# lm3410-sepic-flashlight-driver-17mm-mk-1.net
KiCad netlist of a schematic drawn in EAGLE
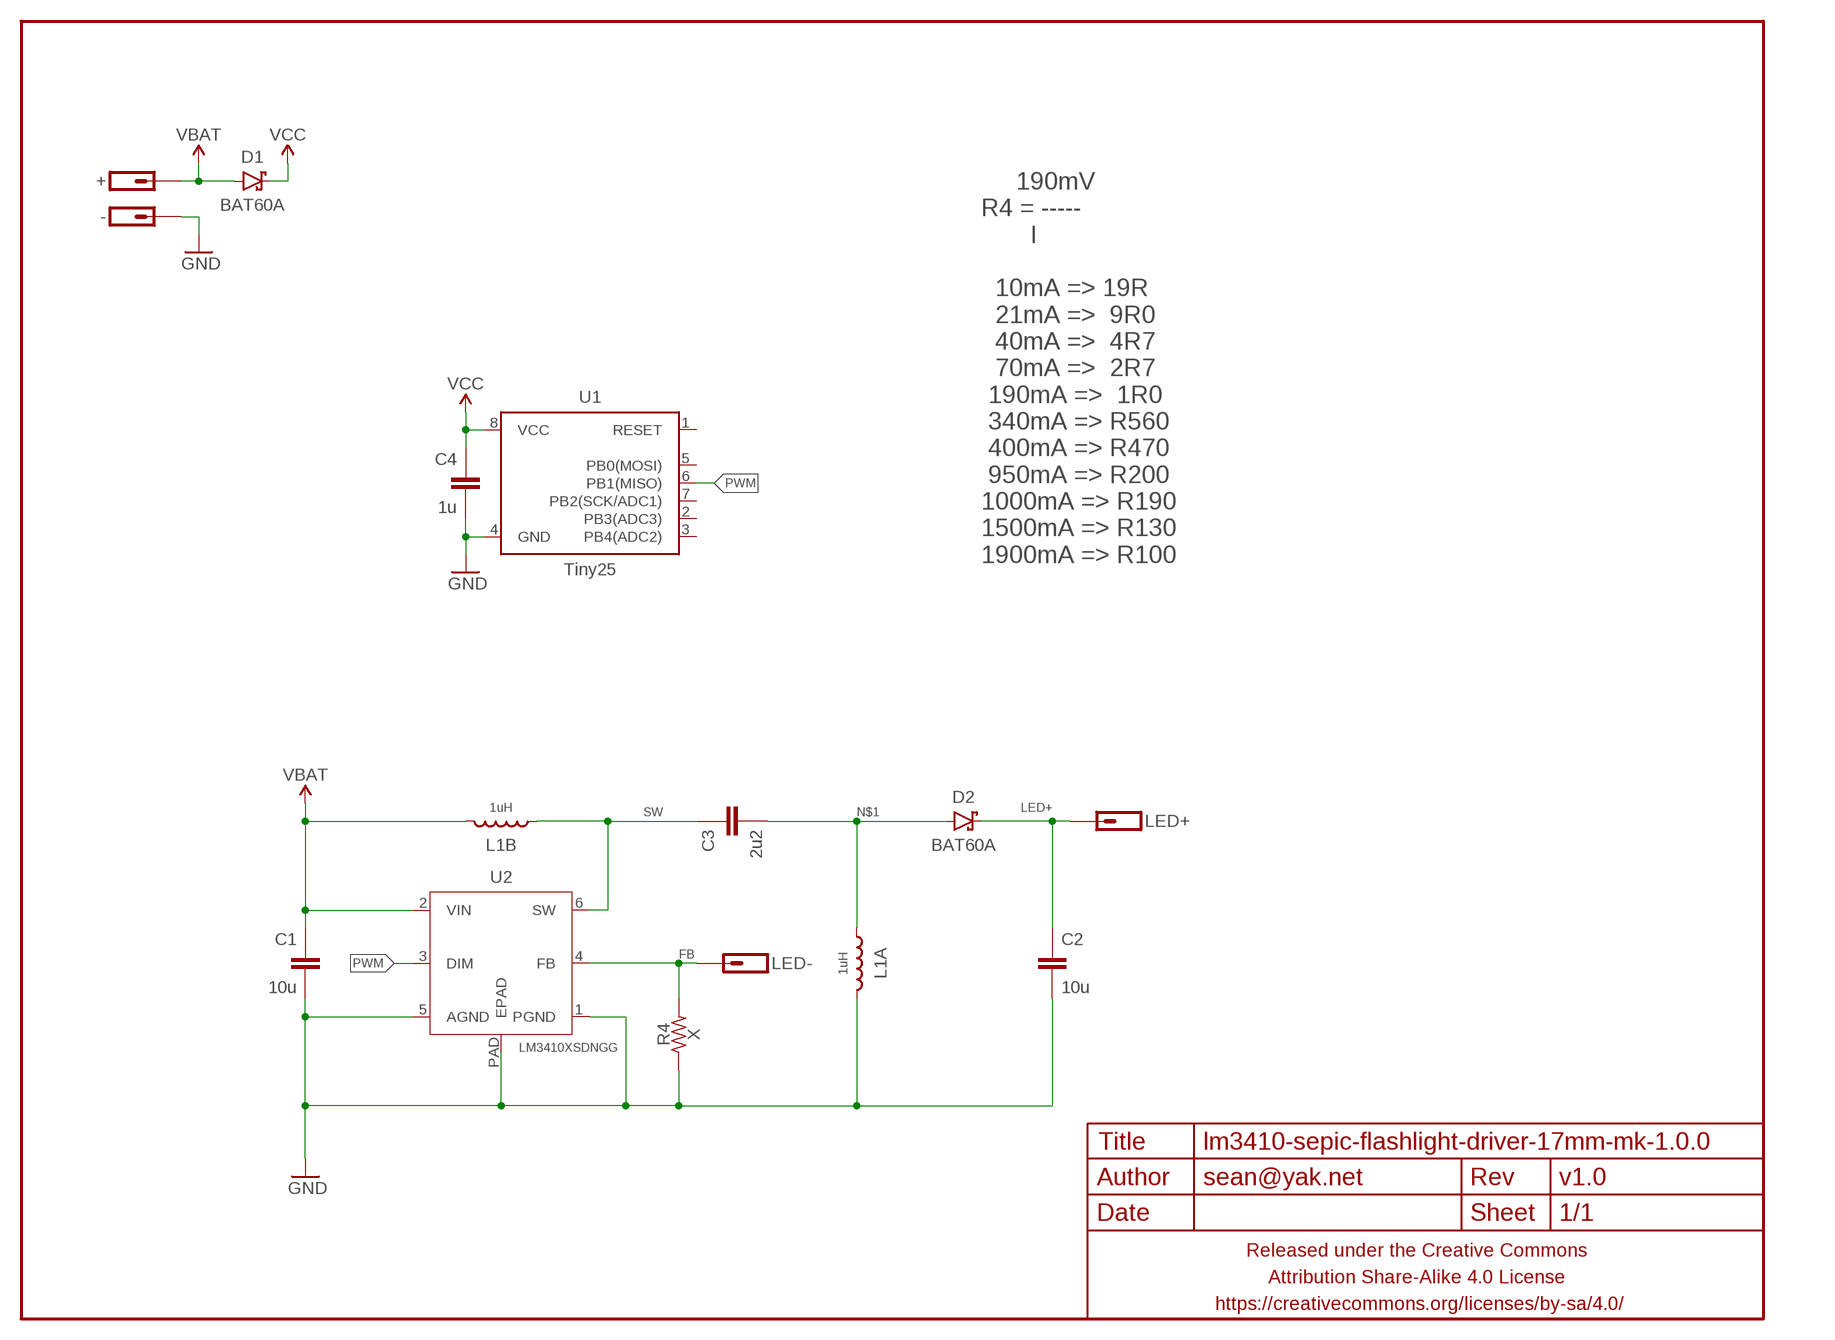
[diagram p0: schematic, sheet 1]

(export (version "E")
  (design (tool "Eeschema 10.0.6"))
  (components
    (comp (ref "+")
      (value "M01NOT-A-VIA-NOPE")
      (footprint "eagle-import:1X01_NOSILK_NOSTOP")
      (libsource (lib "eagle-import") (part "M01NOT-A-VIA-NOPE"))
    )
    (comp (ref "-")
      (value "M01NOT-A-VIA-NOPE")
      (footprint "eagle-import:1X01_NOSILK_NOSTOP")
      (libsource (lib "eagle-import") (part "M01NOT-A-VIA-NOPE"))
    )
    (comp (ref "C1")
      (value "10u")
      (footprint "eagle-import:C0805-TIGHTER")
      (libsource (lib "eagle-import") (part "CAPACITOR-CERAMICC0805-TIGHTER"))
    )
    (comp (ref "C2")
      (value "10u")
      (footprint "eagle-import:C0805-TIGHTER")
      (libsource (lib "eagle-import") (part "CAPACITOR-CERAMICC0805-TIGHTER"))
    )
    (comp (ref "C3")
      (value "2u2")
      (footprint "eagle-import:C0603-TIGHTER")
      (libsource (lib "eagle-import") (part "CAPACITOR-CERAMICC0603-TIGHTER"))
    )
    (comp (ref "C4")
      (value "1u")
      (footprint "eagle-import:C0603-TIGHTER")
      (libsource (lib "eagle-import") (part "CAPACITOR-CERAMICC0603-TIGHTER"))
    )
    (comp (ref "D1")
      (value "BAT60A")
      (footprint "eagle-import:SOD323-SCHOTTKY")
      (libsource (lib "eagle-import") (part "DIODE-SCHOTTKYSOD323"))
    )
    (comp (ref "D2")
      (value "BAT60A")
      (footprint "eagle-import:SOD323-SCHOTTKY")
      (libsource (lib "eagle-import") (part "DIODE-SCHOTTKYSOD323"))
    )
    (comp (ref "FRAME1")
      (value "FRAME-LETTERNO_PACKAGE")
      (footprint "eagle-import:DUMMY")
      (fields (field (name "DESIGNER") "sean@yak.net") (field (name "VERSION") "v1.0"))
      (libsource (lib "eagle-import") (part "FRAME-LETTERNO_PACKAGE"))
    )
    (comp (ref "L1")
      (value "1uH")
      (footprint "eagle-import:LPD5030")
      (libsource (lib "eagle-import") (part "INDUCTOR-DUALCOILCRAFT-LPD5030"))
    )
    (comp (ref "LED+")
      (value "M01PTH-1MM-CIR-NS")
      (footprint "eagle-import:1X01-1MM-CIR-NS")
      (libsource (lib "eagle-import") (part "M01PTH-1MM-CIR-NS"))
    )
    (comp (ref "LED-")
      (value "M01PTH-1MM-CIR-NS")
      (footprint "eagle-import:1X01-1MM-CIR-NS")
      (libsource (lib "eagle-import") (part "M01PTH-1MM-CIR-NS"))
    )
    (comp (ref "R4")
      (value "X")
      (footprint "eagle-import:R0805-TIGHTER")
      (libsource (lib "eagle-import") (part "RESISTORR0805-TIGHTER"))
    )
    (comp (ref "U1")
      (value "Tiny25")
      (footprint "eagle-import:SO08-SKINNYPADS")
      (libsource (lib "eagle-import") (part "ATTINY45TINY25-SOICN-NARROWER"))
    )
    (comp (ref "U2")
      (value "LM3410XSDNGG")
      (footprint "eagle-import:DFN300X300X80-7N")
      (fields (field (name "MPN") "LM3410XSD"))
      (libsource (lib "eagle-import") (part "LM3410XSDNGG"))
    )
  )
  (nets
    (net (code "1") (name "/FB") (class "Default")
      (node (ref "LED-") (pin "1") (pinfunction "1_1") (pintype "passive"))
      (node (ref "R4") (pin "2") (pinfunction "2_2") (pintype "passive"))
      (node (ref "U2") (pin "4") (pinfunction "FB_4") (pintype "input"))
    )
    (net (code "2") (name "/LED+") (class "Default")
      (node (ref "C2") (pin "1") (pinfunction "1_1") (pintype "passive"))
      (node (ref "D2") (pin "C") (pinfunction "C_C") (pintype "passive"))
      (node (ref "LED+") (pin "1") (pinfunction "1_1") (pintype "passive"))
    )
    (net (code "3") (name "/N$1") (class "Default")
      (node (ref "C3") (pin "2") (pinfunction "2_2") (pintype "passive"))
      (node (ref "D2") (pin "A") (pinfunction "A_A") (pintype "passive"))
      (node (ref "L1") (pin "1") (pinfunction "1_1") (pintype "passive"))
    )
    (net (code "4") (name "/SW") (class "Default")
      (node (ref "C3") (pin "1") (pinfunction "1_1") (pintype "passive"))
      (node (ref "L1") (pin "4") (pinfunction "1_4") (pintype "passive"))
      (node (ref "U2") (pin "6") (pinfunction "SW_6") (pintype "output"))
    )
    (net (code "5") (name "GND") (class "Default")
      (node (ref "-") (pin "P$1") (pinfunction "1_P$1") (pintype "passive"))
      (node (ref "C1") (pin "2") (pinfunction "2_2") (pintype "passive"))
      (node (ref "C2") (pin "2") (pinfunction "2_2") (pintype "passive"))
      (node (ref "C4") (pin "2") (pinfunction "2_2") (pintype "passive"))
      (node (ref "L1") (pin "2") (pinfunction "2_2") (pintype "passive"))
      (node (ref "R4") (pin "1") (pinfunction "1_1") (pintype "passive"))
      (node (ref "U1") (pin "4") (pinfunction "GND_4") (pintype "bidirectional"))
      (node (ref "U2") (pin "1") (pinfunction "PGND_1") (pintype "passive"))
      (node (ref "U2") (pin "5") (pinfunction "AGND_5") (pintype "passive"))
      (node (ref "U2") (pin "PAD") (pinfunction "EPAD_PAD") (pintype "passive"))
    )
    (net (code "6") (name "PWM") (class "Default")
      (node (ref "U1") (pin "6") (pinfunction "PB1(MISO)_6") (pintype "bidirectional"))
      (node (ref "U2") (pin "3") (pinfunction "DIM_3") (pintype "input"))
    )
    (net (code "7") (name "VBAT") (class "Default")
      (node (ref "+") (pin "P$1") (pinfunction "1_P$1") (pintype "passive"))
      (node (ref "C1") (pin "1") (pinfunction "1_1") (pintype "passive"))
      (node (ref "D1") (pin "A") (pinfunction "A_A") (pintype "passive"))
      (node (ref "L1") (pin "3") (pinfunction "2_3") (pintype "passive"))
      (node (ref "U2") (pin "2") (pinfunction "VIN_2") (pintype "power_in"))
    )
    (net (code "8") (name "VCC") (class "Default")
      (node (ref "C4") (pin "1") (pinfunction "1_1") (pintype "passive"))
      (node (ref "D1") (pin "C") (pinfunction "C_C") (pintype "passive"))
      (node (ref "U1") (pin "8") (pinfunction "VCC_8") (pintype "bidirectional"))
    )
    (net (code "9") (name "unconnected-(U1-PB0(MOSI)-Pad5)") (class "Default")
      (node (ref "U1") (pin "5") (pinfunction "PB0(MOSI)_5") (pintype "bidirectional"))
    )
    (net (code "10") (name "unconnected-(U1-PB2(SCK{slash}ADC1)-Pad7)") (class "Default")
      (node (ref "U1") (pin "7") (pinfunction "PB2(SCK/ADC1)_7") (pintype "bidirectional"))
    )
    (net (code "11") (name "unconnected-(U1-PB3(ADC3)-Pad2)") (class "Default")
      (node (ref "U1") (pin "2") (pinfunction "PB3(ADC3)_2") (pintype "bidirectional"))
    )
    (net (code "12") (name "unconnected-(U1-PB4(ADC2)-Pad3)") (class "Default")
      (node (ref "U1") (pin "3") (pinfunction "PB4(ADC2)_3") (pintype "bidirectional"))
    )
    (net (code "13") (name "unconnected-(U1-RESET-Pad1)") (class "Default")
      (node (ref "U1") (pin "1") (pinfunction "RESET_1") (pintype "bidirectional"))
    )
  )
)
